# 1x16_to_1x16.net
KiCad netlist of a schematic drawn in EAGLE
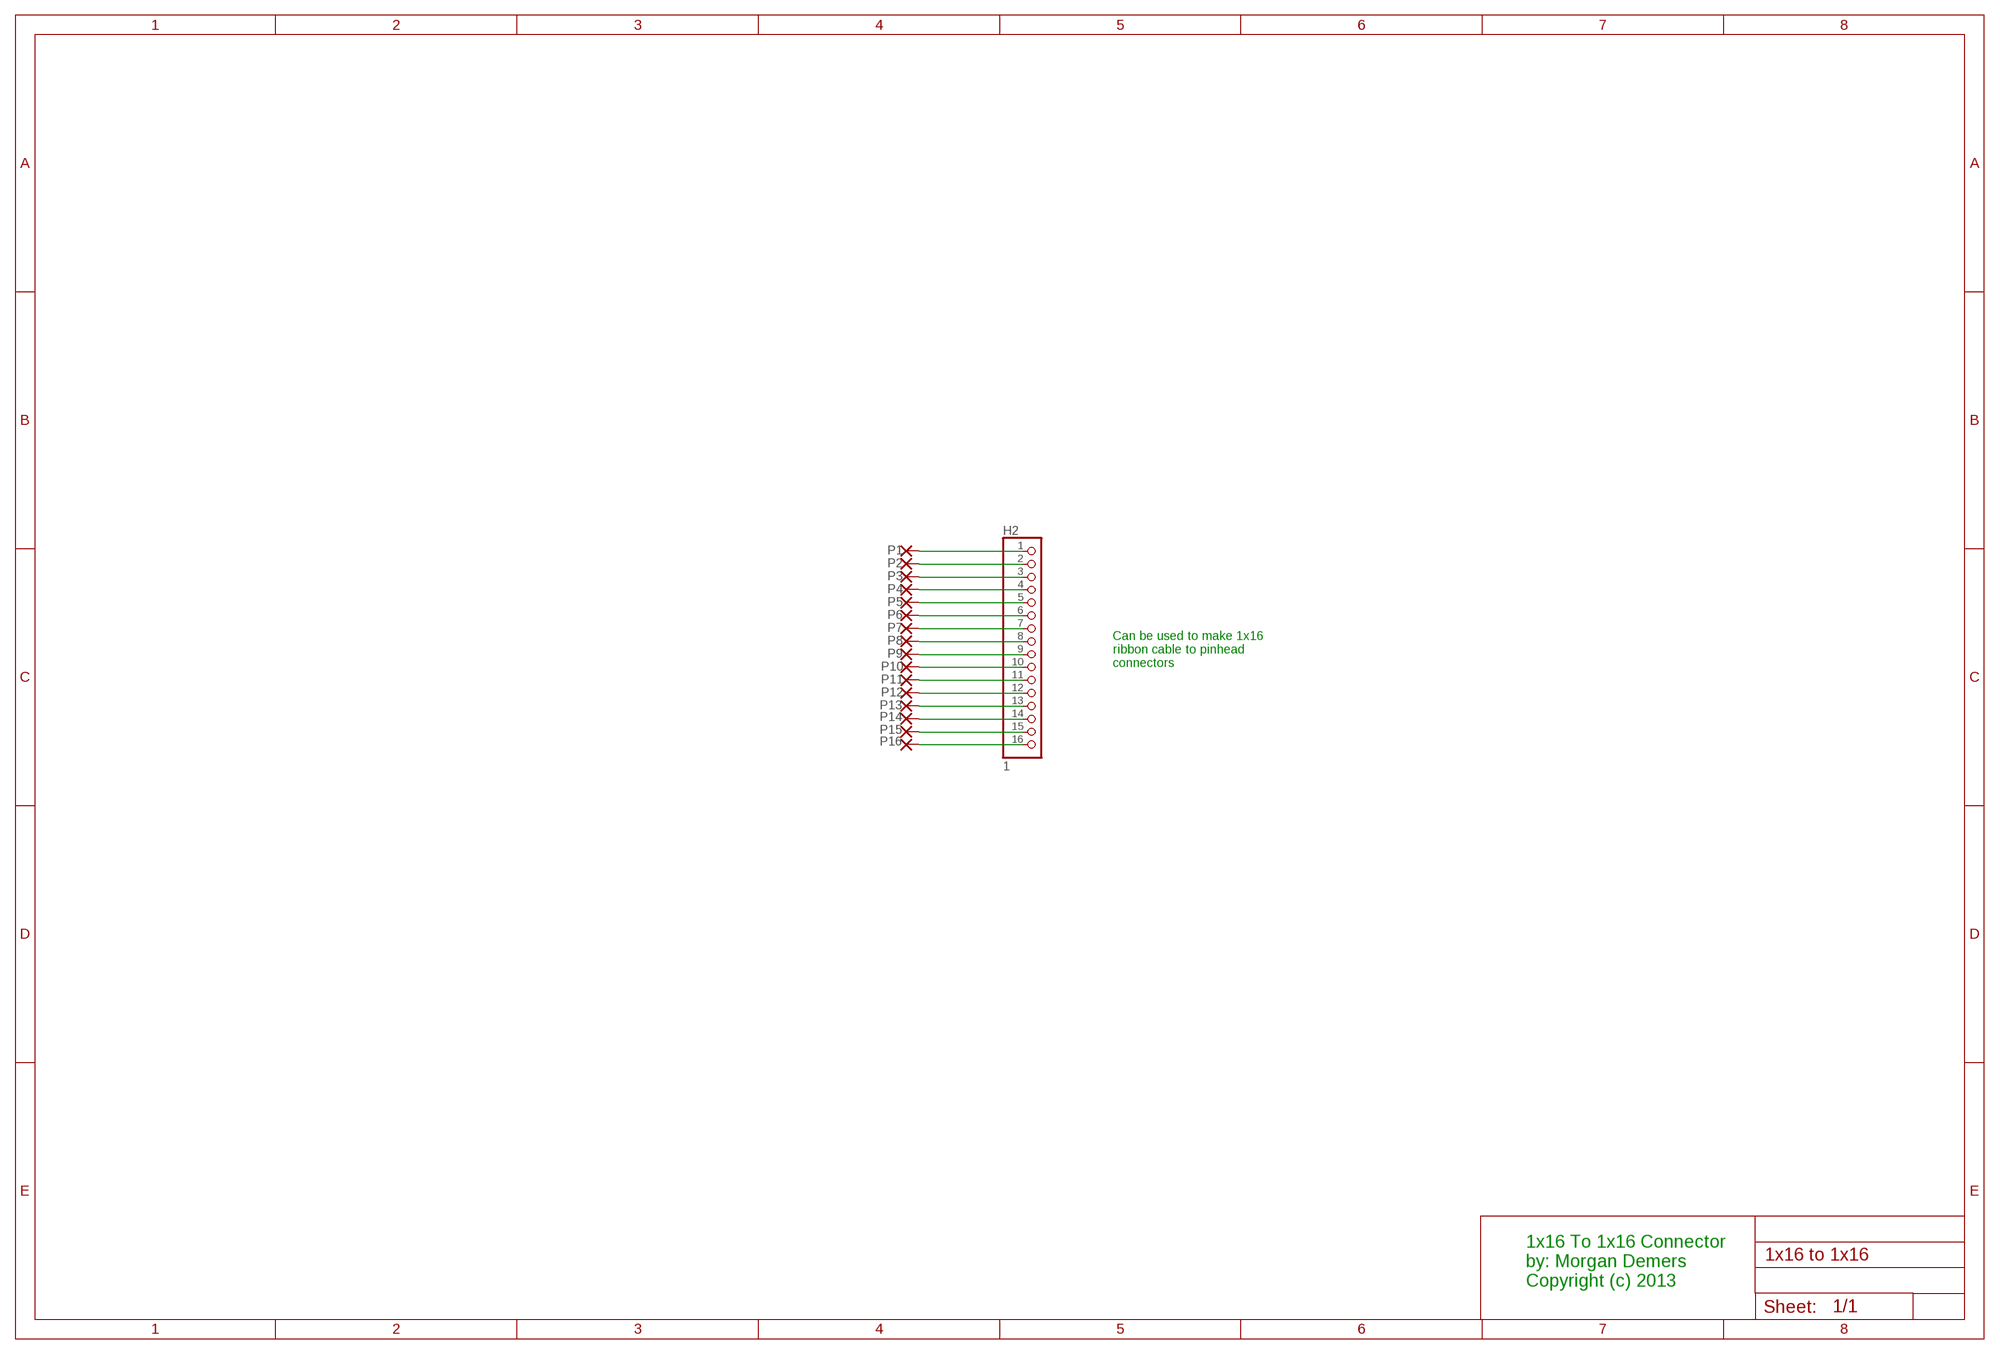
[diagram p0: schematic, sheet 1]

(export (version "E")
  (design (tool "Eeschema 10.0.6"))
  (components
    (comp (ref "H2")
      (value "1")
      (footprint "eagle-import:1X16")
      (libsource (lib "eagle-import") (part "PINHD-1X16"))
    )
    (comp (ref "P1")
      (value "1,6/0,9")
      (footprint "eagle-import:1,6_0,9")
      (libsource (lib "eagle-import") (part "1,6/0,9"))
    )
    (comp (ref "P2")
      (value "1,6/0,9")
      (footprint "eagle-import:1,6_0,9")
      (libsource (lib "eagle-import") (part "1,6/0,9"))
    )
    (comp (ref "P3")
      (value "1,6/0,9")
      (footprint "eagle-import:1,6_0,9")
      (libsource (lib "eagle-import") (part "1,6/0,9"))
    )
    (comp (ref "P4")
      (value "1,6/0,9")
      (footprint "eagle-import:1,6_0,9")
      (libsource (lib "eagle-import") (part "1,6/0,9"))
    )
    (comp (ref "P5")
      (value "1,6/0,9")
      (footprint "eagle-import:1,6_0,9")
      (libsource (lib "eagle-import") (part "1,6/0,9"))
    )
    (comp (ref "P6")
      (value "1,6/0,9")
      (footprint "eagle-import:1,6_0,9")
      (libsource (lib "eagle-import") (part "1,6/0,9"))
    )
    (comp (ref "P7")
      (value "1,6/0,9")
      (footprint "eagle-import:1,6_0,9")
      (libsource (lib "eagle-import") (part "1,6/0,9"))
    )
    (comp (ref "P8")
      (value "1,6/0,9")
      (footprint "eagle-import:1,6_0,9")
      (libsource (lib "eagle-import") (part "1,6/0,9"))
    )
    (comp (ref "P9")
      (value "1,6/0,9")
      (footprint "eagle-import:1,6_0,9")
      (libsource (lib "eagle-import") (part "1,6/0,9"))
    )
    (comp (ref "P10")
      (value "1,6/0,9")
      (footprint "eagle-import:1,6_0,9")
      (libsource (lib "eagle-import") (part "1,6/0,9"))
    )
    (comp (ref "P11")
      (value "1,6/0,9")
      (footprint "eagle-import:1,6_0,9")
      (libsource (lib "eagle-import") (part "1,6/0,9"))
    )
    (comp (ref "P12")
      (value "1,6/0,9")
      (footprint "eagle-import:1,6_0,9")
      (libsource (lib "eagle-import") (part "1,6/0,9"))
    )
    (comp (ref "P13")
      (value "1,6/0,9")
      (footprint "eagle-import:1,6_0,9")
      (libsource (lib "eagle-import") (part "1,6/0,9"))
    )
    (comp (ref "P14")
      (value "1,6/0,9")
      (footprint "eagle-import:1,6_0,9")
      (libsource (lib "eagle-import") (part "1,6/0,9"))
    )
    (comp (ref "P15")
      (value "1,6/0,9")
      (footprint "eagle-import:1,6_0,9")
      (libsource (lib "eagle-import") (part "1,6/0,9"))
    )
    (comp (ref "P16")
      (value "1,6/0,9")
      (footprint "eagle-import:1,6_0,9")
      (libsource (lib "eagle-import") (part "1,6/0,9"))
    )
  )
  (nets
    (net (code "1") (name "Net-(P1-P)") (class "Default")
      (node (ref "H2") (pin "1") (pinfunction "1_1") (pintype "passive"))
      (node (ref "P1") (pin "1") (pinfunction "P_1") (pintype "passive"))
    )
    (net (code "2") (name "Net-(P2-P)") (class "Default")
      (node (ref "H2") (pin "2") (pinfunction "2_2") (pintype "passive"))
      (node (ref "P2") (pin "1") (pinfunction "P_1") (pintype "passive"))
    )
    (net (code "3") (name "Net-(P3-P)") (class "Default")
      (node (ref "H2") (pin "3") (pinfunction "3_3") (pintype "passive"))
      (node (ref "P3") (pin "1") (pinfunction "P_1") (pintype "passive"))
    )
    (net (code "4") (name "Net-(P4-P)") (class "Default")
      (node (ref "H2") (pin "4") (pinfunction "4_4") (pintype "passive"))
      (node (ref "P4") (pin "1") (pinfunction "P_1") (pintype "passive"))
    )
    (net (code "5") (name "Net-(P5-P)") (class "Default")
      (node (ref "H2") (pin "5") (pinfunction "5_5") (pintype "passive"))
      (node (ref "P5") (pin "1") (pinfunction "P_1") (pintype "passive"))
    )
    (net (code "6") (name "Net-(P6-P)") (class "Default")
      (node (ref "H2") (pin "6") (pinfunction "6_6") (pintype "passive"))
      (node (ref "P6") (pin "1") (pinfunction "P_1") (pintype "passive"))
    )
    (net (code "7") (name "Net-(P7-P)") (class "Default")
      (node (ref "H2") (pin "7") (pinfunction "7_7") (pintype "passive"))
      (node (ref "P7") (pin "1") (pinfunction "P_1") (pintype "passive"))
    )
    (net (code "8") (name "Net-(P8-P)") (class "Default")
      (node (ref "H2") (pin "8") (pinfunction "8_8") (pintype "passive"))
      (node (ref "P8") (pin "1") (pinfunction "P_1") (pintype "passive"))
    )
    (net (code "9") (name "Net-(P9-P)") (class "Default")
      (node (ref "H2") (pin "9") (pinfunction "9_9") (pintype "passive"))
      (node (ref "P9") (pin "1") (pinfunction "P_1") (pintype "passive"))
    )
    (net (code "10") (name "Net-(P10-P)") (class "Default")
      (node (ref "H2") (pin "10") (pinfunction "10_10") (pintype "passive"))
      (node (ref "P10") (pin "1") (pinfunction "P_1") (pintype "passive"))
    )
    (net (code "11") (name "Net-(P11-P)") (class "Default")
      (node (ref "H2") (pin "11") (pinfunction "11_11") (pintype "passive"))
      (node (ref "P11") (pin "1") (pinfunction "P_1") (pintype "passive"))
    )
    (net (code "12") (name "Net-(P12-P)") (class "Default")
      (node (ref "H2") (pin "12") (pinfunction "12_12") (pintype "passive"))
      (node (ref "P12") (pin "1") (pinfunction "P_1") (pintype "passive"))
    )
    (net (code "13") (name "Net-(P13-P)") (class "Default")
      (node (ref "H2") (pin "13") (pinfunction "13_13") (pintype "passive"))
      (node (ref "P13") (pin "1") (pinfunction "P_1") (pintype "passive"))
    )
    (net (code "14") (name "Net-(P14-P)") (class "Default")
      (node (ref "H2") (pin "14") (pinfunction "14_14") (pintype "passive"))
      (node (ref "P14") (pin "1") (pinfunction "P_1") (pintype "passive"))
    )
    (net (code "15") (name "Net-(P15-P)") (class "Default")
      (node (ref "H2") (pin "15") (pinfunction "15_15") (pintype "passive"))
      (node (ref "P15") (pin "1") (pinfunction "P_1") (pintype "passive"))
    )
    (net (code "16") (name "Net-(P16-P)") (class "Default")
      (node (ref "H2") (pin "16") (pinfunction "16_16") (pintype "passive"))
      (node (ref "P16") (pin "1") (pinfunction "P_1") (pintype "passive"))
    )
  )
)
